# STM32.net
KiCad netlist of a schematic drawn in EasyEDA Pro
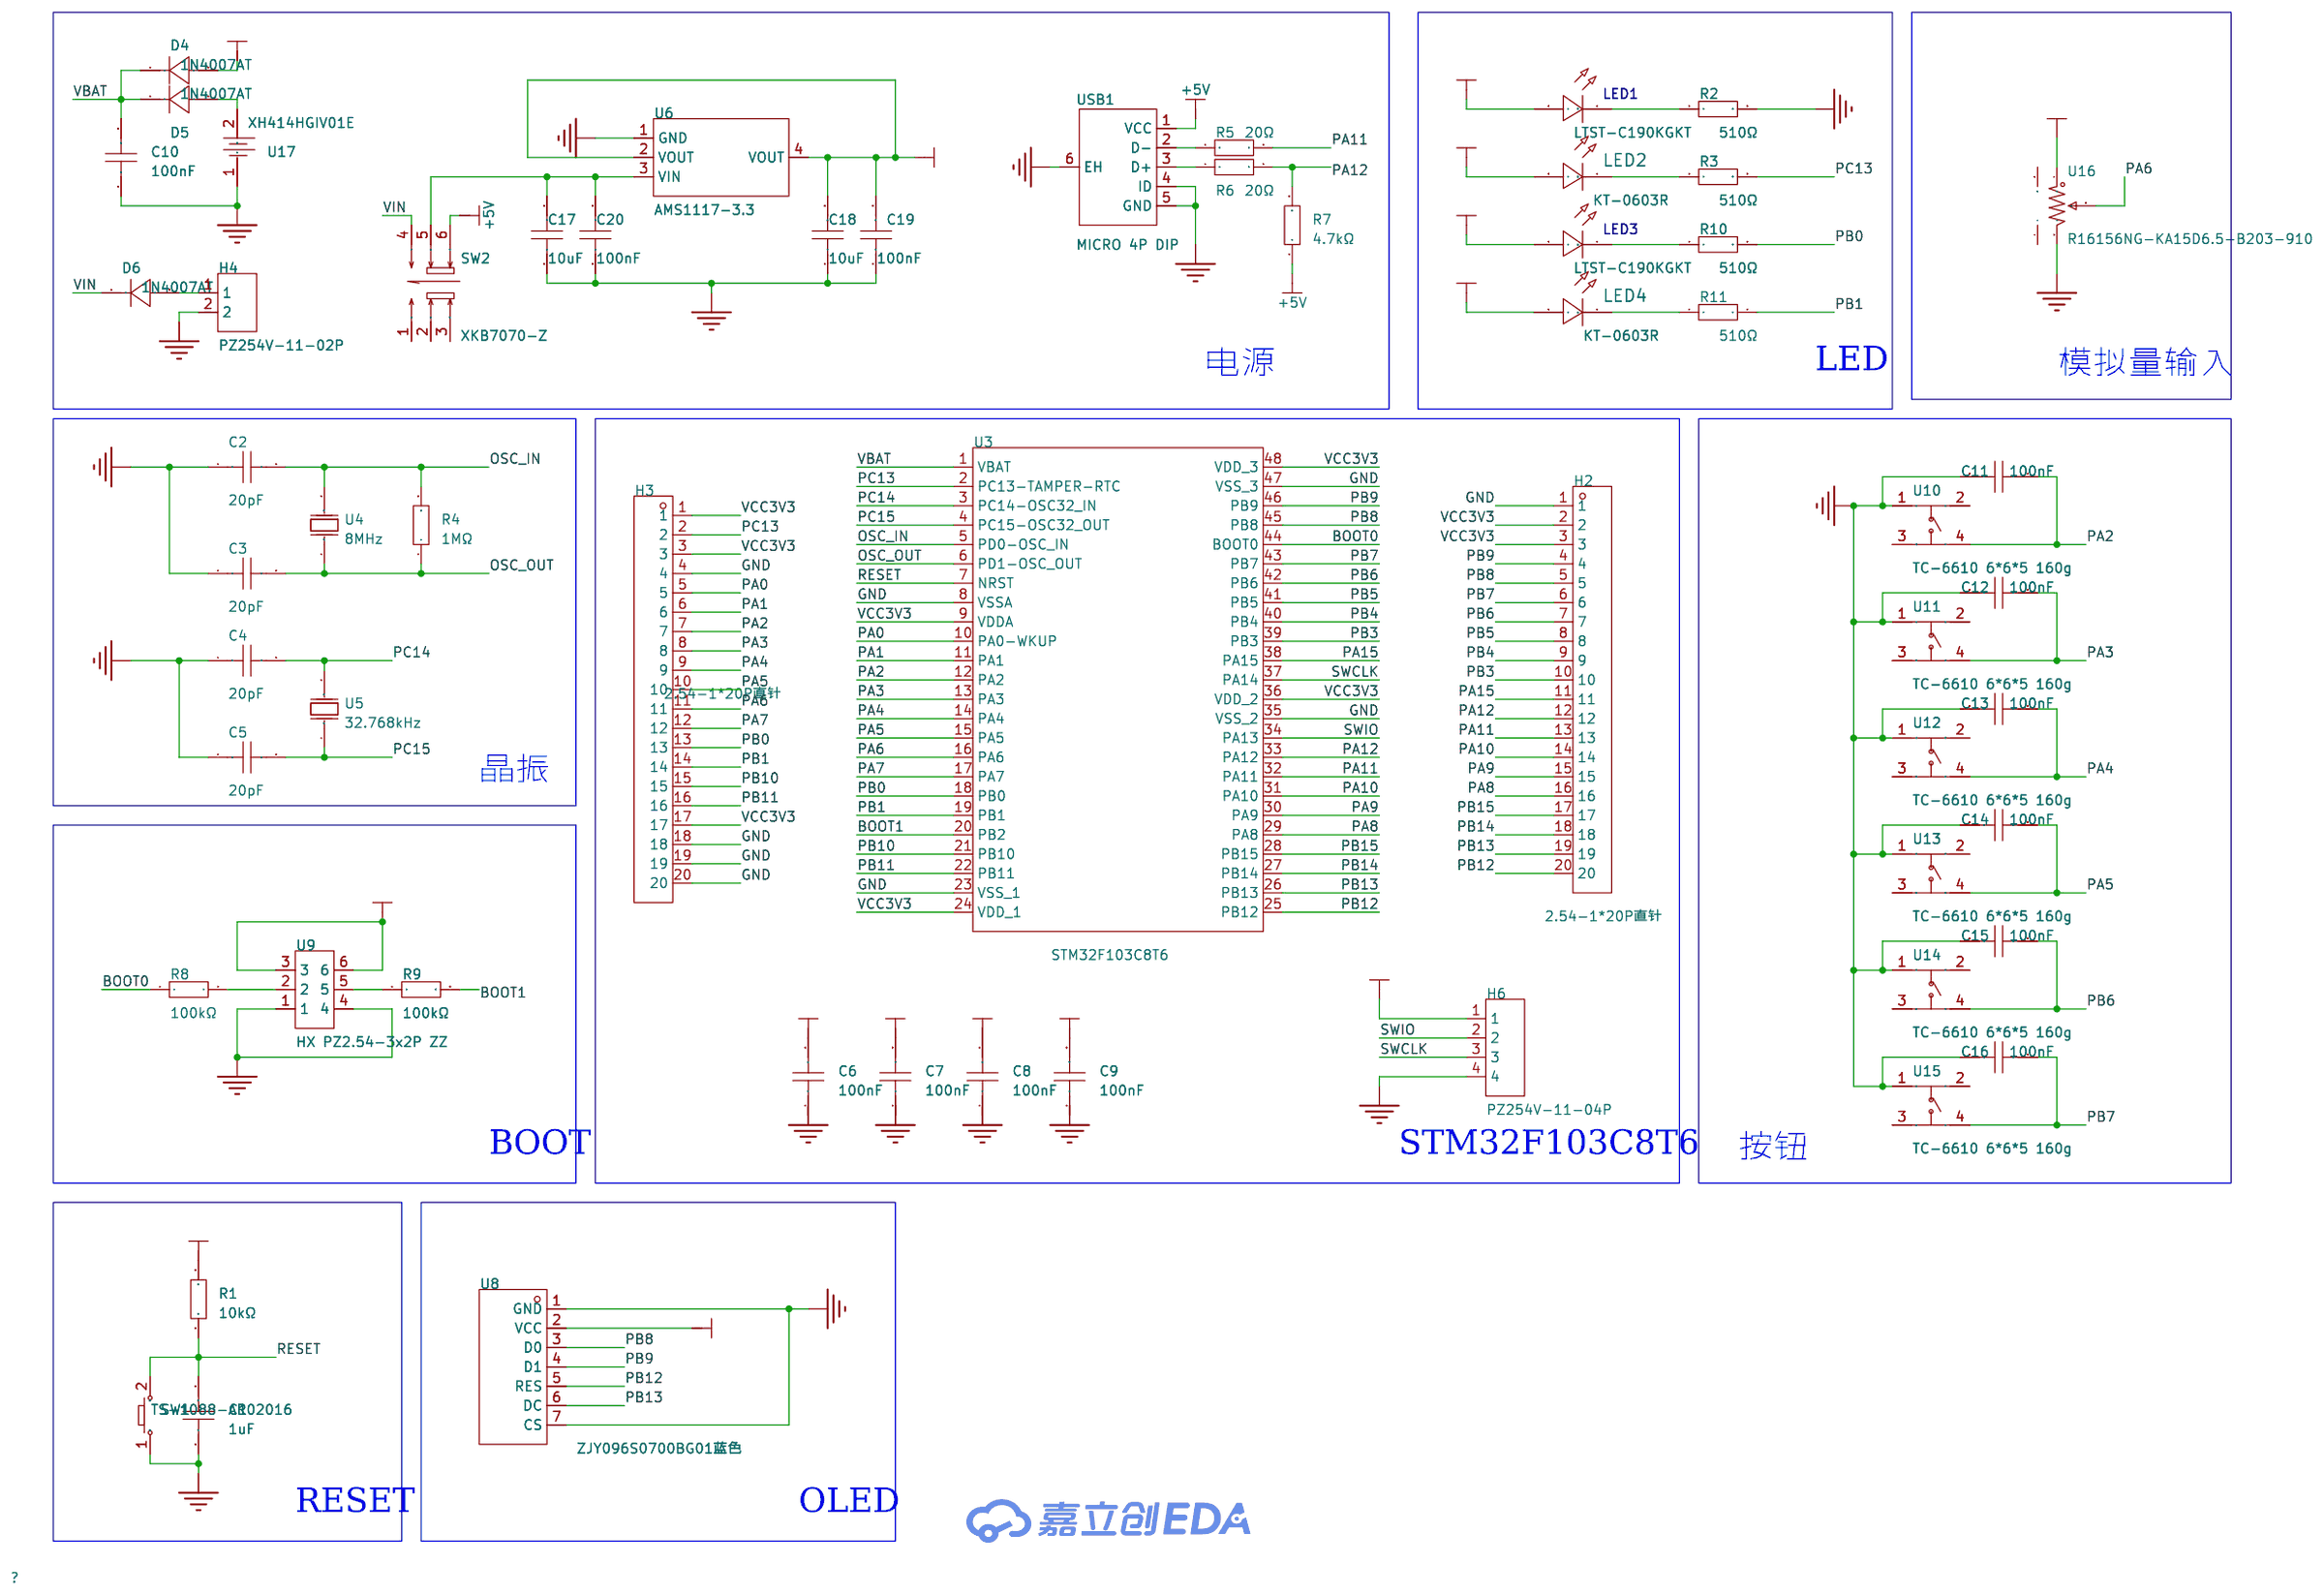
[diagram p0: schematic sheet]

(export (version "E")
  (design (tool "Eeschema 10.0.6"))
  (components
    (comp (ref "C1")
      (value "1uF")
      (footprint "easyedapro:C0603")
      (fields
        (field (name "Manufacturer Part") "CL10A105KO8NNNC")
        (field (name "Manufacturer") "SAMSUNG(三星)")
      )
      (libsource (lib "easyedapro") (part "Capacitance"))
    )
    (comp (ref "C2")
      (value "20pF")
      (footprint "easyedapro:C0603")
      (fields
        (field (name "Manufacturer Part") "CC0603JRNPO9BN200")
        (field (name "Manufacturer") "YAGEO(国巨)")
      )
      (libsource (lib "easyedapro") (part "Capacitance"))
    )
    (comp (ref "C3")
      (value "20pF")
      (footprint "easyedapro:C0603")
      (fields
        (field (name "Manufacturer Part") "CC0603JRNPO9BN200")
        (field (name "Manufacturer") "YAGEO(国巨)")
      )
      (libsource (lib "easyedapro") (part "Capacitance"))
    )
    (comp (ref "C4")
      (value "20pF")
      (footprint "easyedapro:C0603")
      (fields
        (field (name "Manufacturer Part") "CC0603JRNPO9BN200")
        (field (name "Manufacturer") "YAGEO(国巨)")
      )
      (libsource (lib "easyedapro") (part "Capacitance"))
    )
    (comp (ref "C5")
      (value "20pF")
      (footprint "easyedapro:C0603")
      (fields
        (field (name "Manufacturer Part") "CC0603JRNPO9BN200")
        (field (name "Manufacturer") "YAGEO(国巨)")
      )
      (libsource (lib "easyedapro") (part "Capacitance"))
    )
    (comp (ref "C6")
      (value "100nF")
      (footprint "easyedapro:C0603")
      (fields
        (field (name "Manufacturer Part") "CGA0603X7R104K500JT")
        (field (name "Manufacturer") "HRE(芯声)")
      )
      (libsource (lib "easyedapro") (part "Capacitance"))
    )
    (comp (ref "C7")
      (value "100nF")
      (footprint "easyedapro:C0603")
      (fields
        (field (name "Manufacturer Part") "CGA0603X7R104K500JT")
        (field (name "Manufacturer") "HRE(芯声)")
      )
      (libsource (lib "easyedapro") (part "Capacitance"))
    )
    (comp (ref "C8")
      (value "100nF")
      (footprint "easyedapro:C0603")
      (fields
        (field (name "Manufacturer Part") "CGA0603X7R104K500JT")
        (field (name "Manufacturer") "HRE(芯声)")
      )
      (libsource (lib "easyedapro") (part "Capacitance"))
    )
    (comp (ref "C9")
      (value "100nF")
      (footprint "easyedapro:C0603")
      (fields
        (field (name "Manufacturer Part") "CGA0603X7R104K500JT")
        (field (name "Manufacturer") "HRE(芯声)")
      )
      (libsource (lib "easyedapro") (part "Capacitance"))
    )
    (comp (ref "C10")
      (value "100nF")
      (footprint "easyedapro:C0603")
      (fields
        (field (name "Manufacturer Part") "CGA0603X7R104K500JT")
        (field (name "Manufacturer") "HRE(芯声)")
      )
      (libsource (lib "easyedapro") (part "Capacitance"))
    )
    (comp (ref "C11")
      (value "100nF")
      (footprint "easyedapro:C0603")
      (fields
        (field (name "Manufacturer Part") "CL10B104KA8NNNC")
        (field (name "Manufacturer") "SAMSUNG(三星)")
      )
      (libsource (lib "easyedapro") (part "Capacitance"))
    )
    (comp (ref "C12")
      (value "100nF")
      (footprint "easyedapro:C0603")
      (fields
        (field (name "Manufacturer Part") "CL10B104KA8NNNC")
        (field (name "Manufacturer") "SAMSUNG(三星)")
      )
      (libsource (lib "easyedapro") (part "Capacitance"))
    )
    (comp (ref "C13")
      (value "100nF")
      (footprint "easyedapro:C0603")
      (fields
        (field (name "Manufacturer Part") "CL10B104KA8NNNC")
        (field (name "Manufacturer") "SAMSUNG(三星)")
      )
      (libsource (lib "easyedapro") (part "Capacitance"))
    )
    (comp (ref "C14")
      (value "100nF")
      (footprint "easyedapro:C0603")
      (fields
        (field (name "Manufacturer Part") "CL10B104KA8NNNC")
        (field (name "Manufacturer") "SAMSUNG(三星)")
      )
      (libsource (lib "easyedapro") (part "Capacitance"))
    )
    (comp (ref "C15")
      (value "100nF")
      (footprint "easyedapro:C0603")
      (fields
        (field (name "Manufacturer Part") "CL10B104KA8NNNC")
        (field (name "Manufacturer") "SAMSUNG(三星)")
      )
      (libsource (lib "easyedapro") (part "Capacitance"))
    )
    (comp (ref "C16")
      (value "100nF")
      (footprint "easyedapro:C0603")
      (fields
        (field (name "Manufacturer Part") "CL10B104KA8NNNC")
        (field (name "Manufacturer") "SAMSUNG(三星)")
      )
      (libsource (lib "easyedapro") (part "Capacitance"))
    )
    (comp (ref "C17")
      (value "10uF")
      (footprint "easyedapro:C0603")
      (fields
        (field (name "Manufacturer Part") "CL10A106KP8NNNC")
        (field (name "Manufacturer") "SAMSUNG(三星)")
      )
      (libsource (lib "easyedapro") (part "Capacitance"))
    )
    (comp (ref "C18")
      (value "10uF")
      (footprint "easyedapro:C0603")
      (fields
        (field (name "Manufacturer Part") "CL10A106KP8NNNC")
        (field (name "Manufacturer") "SAMSUNG(三星)")
      )
      (libsource (lib "easyedapro") (part "Capacitance"))
    )
    (comp (ref "C19")
      (value "100nF")
      (footprint "easyedapro:C0603")
      (fields
        (field (name "Manufacturer Part") "CL10B104KA8NNNC")
        (field (name "Manufacturer") "SAMSUNG(三星)")
      )
      (libsource (lib "easyedapro") (part "Capacitance"))
    )
    (comp (ref "C20")
      (value "100nF")
      (footprint "easyedapro:C0603")
      (fields
        (field (name "Manufacturer Part") "CL10B104KA8NNNC")
        (field (name "Manufacturer") "SAMSUNG(三星)")
      )
      (libsource (lib "easyedapro") (part "Capacitance"))
    )
    (comp (ref "D4")
      (value "1N4007AT")
      (footprint "easyedapro:DO_1N4007")
      (fields (field (name "Manufacturer") "Agertech(艾吉芯)"))
      (libsource (lib "easyedapro") (part "D_1N4007"))
    )
    (comp (ref "D5")
      (value "1N4007AT")
      (footprint "easyedapro:DO_1N4007")
      (fields (field (name "Manufacturer") "Agertech(艾吉芯)"))
      (libsource (lib "easyedapro") (part "D_1N4007"))
    )
    (comp (ref "D6")
      (value "1N4007AT")
      (footprint "easyedapro:DO_1N4007")
      (fields (field (name "Manufacturer") "Agertech(艾吉芯)"))
      (libsource (lib "easyedapro") (part "D_1N4007"))
    )
    (comp (ref "H2")
      (value "2.54-1*20P直针")
      (footprint "easyedapro:HDR-TH_20P-P2.54-V-M-1")
      (fields (field (name "Manufacturer") "BOOMELE(博穆精密)"))
      (libsource (lib "easyedapro") (part "HDR_2.54-1x20P"))
    )
    (comp (ref "H3")
      (value "2.54-1*20P直针")
      (footprint "easyedapro:HDR-TH_20P-P2.54-V-M-1")
      (fields (field (name "Manufacturer") "BOOMELE(博穆精密)"))
      (libsource (lib "easyedapro") (part "HDR_2.54-1x20P"))
    )
    (comp (ref "H4")
      (value "PZ254V-11-02P")
      (footprint "easyedapro:HDR-TH_2P-P2.54-V-M")
      (fields (field (name "Manufacturer") "XFCN(兴飞)"))
      (libsource (lib "easyedapro") (part "PZ254V-11-02P"))
    )
    (comp (ref "H6")
      (value "PZ254V-11-04P")
      (footprint "easyedapro:HDR-TH_4P-P2.54-V-M")
      (fields (field (name "Manufacturer") "XFCN(兴飞)"))
      (libsource (lib "easyedapro") (part "PZ254V-11-04P"))
    )
    (comp (ref "LED1")
      (value "LTST-C190KGKT")
      (footprint "easyedapro:LED_0603")
      (fields (field (name "Manufacturer") "LITEON(光宝)"))
      (libsource (lib "easyedapro") (part "LED_G"))
    )
    (comp (ref "LED2")
      (value "KT-0603R")
      (footprint "easyedapro:LED_0603")
      (fields (field (name "Manufacturer") "KENTO"))
      (libsource (lib "easyedapro") (part "LED_R"))
    )
    (comp (ref "LED3")
      (value "LTST-C190KGKT")
      (footprint "easyedapro:LED_0603")
      (fields (field (name "Manufacturer") "LITEON(光宝)"))
      (libsource (lib "easyedapro") (part "LED_G"))
    )
    (comp (ref "LED4")
      (value "KT-0603R")
      (footprint "easyedapro:LED_0603")
      (fields (field (name "Manufacturer") "KENTO"))
      (libsource (lib "easyedapro") (part "LED_R"))
    )
    (comp (ref "R1")
      (value "10kΩ")
      (footprint "easyedapro:R0603")
      (fields
        (field (name "Manufacturer Part") "0603WAF1002T5E")
        (field (name "Manufacturer") "UNI-ROYAL(厚声)")
      )
      (libsource (lib "easyedapro") (part "电阻"))
    )
    (comp (ref "R2")
      (value "510Ω")
      (footprint "easyedapro:R0603")
      (fields
        (field (name "Manufacturer Part") "0603WAF5100T5E")
        (field (name "Manufacturer") "UNI-ROYAL(厚声)")
      )
      (libsource (lib "easyedapro") (part "电阻"))
    )
    (comp (ref "R3")
      (value "510Ω")
      (footprint "easyedapro:R0603")
      (fields
        (field (name "Manufacturer Part") "0603WAF5100T5E")
        (field (name "Manufacturer") "UNI-ROYAL(厚声)")
      )
      (libsource (lib "easyedapro") (part "电阻"))
    )
    (comp (ref "R4")
      (value "1MΩ")
      (footprint "easyedapro:R0603")
      (fields
        (field (name "Manufacturer Part") "0603WAF1004T5E")
        (field (name "Manufacturer") "UNI-ROYAL(厚声)")
      )
      (libsource (lib "easyedapro") (part "电阻"))
    )
    (comp (ref "R5")
      (value "20Ω")
      (footprint "easyedapro:R0603")
      (fields
        (field (name "Manufacturer Part") "0603WAF200JT5E")
        (field (name "Manufacturer") "UNI-ROYAL(厚声)")
      )
      (libsource (lib "easyedapro") (part "电阻"))
    )
    (comp (ref "R6")
      (value "20Ω")
      (footprint "easyedapro:R0603")
      (fields
        (field (name "Manufacturer Part") "0603WAF200JT5E")
        (field (name "Manufacturer") "UNI-ROYAL(厚声)")
      )
      (libsource (lib "easyedapro") (part "电阻"))
    )
    (comp (ref "R7")
      (value "4.7kΩ")
      (footprint "easyedapro:R0603")
      (fields
        (field (name "Manufacturer Part") "0603WAF4701T5E")
        (field (name "Manufacturer") "UNI-ROYAL(厚声)")
      )
      (libsource (lib "easyedapro") (part "电阻"))
    )
    (comp (ref "R8")
      (value "100kΩ")
      (footprint "easyedapro:R0603")
      (fields
        (field (name "Manufacturer Part") "0603WAF1003T5E")
        (field (name "Manufacturer") "UNI-ROYAL(厚声)")
      )
      (libsource (lib "easyedapro") (part "电阻"))
    )
    (comp (ref "R9")
      (value "100kΩ")
      (footprint "easyedapro:R0603")
      (fields
        (field (name "Manufacturer Part") "0603WAF1003T5E")
        (field (name "Manufacturer") "UNI-ROYAL(厚声)")
      )
      (libsource (lib "easyedapro") (part "电阻"))
    )
    (comp (ref "R10")
      (value "510Ω")
      (footprint "easyedapro:R0603")
      (fields
        (field (name "Manufacturer Part") "0603WAF5100T5E")
        (field (name "Manufacturer") "UNI-ROYAL(厚声)")
      )
      (libsource (lib "easyedapro") (part "电阻"))
    )
    (comp (ref "R11")
      (value "510Ω")
      (footprint "easyedapro:R0603")
      (fields
        (field (name "Manufacturer Part") "0603WAF5100T5E")
        (field (name "Manufacturer") "UNI-ROYAL(厚声)")
      )
      (libsource (lib "easyedapro") (part "电阻"))
    )
    (comp (ref "SW1")
      (value "TS-1088-AR02016")
      (footprint "easyedapro:Key_SMD_3x4x2")
      (fields (field (name "Manufacturer") "XUNPU(讯普)"))
      (libsource (lib "easyedapro") (part "轻触按键x2"))
    )
    (comp (ref "SW2")
      (value "XKB7070-Z")
      (footprint "easyedapro:SW-TH_6P-L7.0-W7.0-P2.00")
      (description "自锁/无锁:自锁;安装方式:直插;触点电流:100mA;额定电压 (AC):250V;额定电压 (DC):30V;带灯:不带;作用力:160gf;机械寿命:10万次;")
      (fields (field (name "Manufacturer") "XKB Connectivity(中国星坤)"))
      (libsource (lib "easyedapro") (part "XKB7070-Z"))
    )
    (comp (ref "U3")
      (value "STM32F103C8T6")
      (footprint "easyedapro:LQFP-48_L7.0-W7.0-P0.50-LS9.0-BL")
      (description "CPU内核:ARM-M3;CPU最大主频:72MHz;应用领域:-;")
      (fields (field (name "Manufacturer") "ST(意法半导体)"))
      (libsource (lib "easyedapro") (part "STM32F103C8T6"))
    )
    (comp (ref "U4")
      (value "8MHz")
      (footprint "easyedapro:HC-49S_L11.5-W5.0-P4.88")
      (description "频率:8MHz;常温频差:±20ppm;外接负载电容:20pF;频率稳定度(全温):±30ppm;")
      (fields (field (name "Manufacturer Part") "RB080001184") (field (name "Manufacturer") "TROQ(创捷)"))
      (libsource (lib "easyedapro") (part "RB080001184"))
    )
    (comp (ref "U5")
      (value "32.768kHz")
      (footprint "easyedapro:CRYSTAL-SMD_L3.2-W1.5")
      (description "晶振类型:贴片晶振;频率:32.768kHz;常温频差:±10ppm;外接负载电容:12.5pF;")
      (fields (field (name "Manufacturer Part") "RNE32768082") (field (name "Manufacturer") "TROQ(创捷)"))
      (libsource (lib "easyedapro") (part "RNE32768082"))
    )
    (comp (ref "U6")
      (value "AMS1117-3.3")
      (footprint "easyedapro:SOT-223-3_L6.5-W3.4-P2.30-LS7.0-BR")
      (description "输出类型:固定;工作电压:16V;输出电压:3.3V;输出电流:1A;电源纹波抑制比(PSRR):72dB@(120Hz);输出极性:正极;")
      (fields (field (name "Manufacturer") "AMS"))
      (libsource (lib "easyedapro") (part "AMS1117-3.3"))
    )
    (comp (ref "U8")
      (value "ZJY096S0700BG01蓝色")
      (footprint "easyedapro:OLED-TH_OLED0.96-SPI")
      (libsource (lib "easyedapro") (part "ZJY096S0700BG01蓝色"))
    )
    (comp (ref "U9")
      (value "HX PZ2.54-3x2P ZZ")
      (footprint "easyedapro:HDR-TH_6P-P2.54-V-M-R3-C2-S2.54_2")
      (fields (field (name "Manufacturer") "hanxia(韩下)"))
      (libsource (lib "easyedapro") (part "HX PZ2.54-3X2P ZZ"))
    )
    (comp (ref "U10")
      (value "TC-6610 6*6*5 160g")
      (footprint "easyedapro:SW-TH_4P-L6.0-W6.0-P4.50-LS6.5")
      (description "轻触开关  6*6*5 160g力 4.3基座 复银 耐温 ROHS")
      (fields (field (name "Manufacturer") "FG(富港)"))
      (libsource (lib "easyedapro") (part "TC-6610 6*6*5 160G"))
    )
    (comp (ref "U11")
      (value "TC-6610 6*6*5 160g")
      (footprint "easyedapro:SW-TH_4P-L6.0-W6.0-P4.50-LS6.5")
      (description "轻触开关  6*6*5 160g力 4.3基座 复银 耐温 ROHS")
      (fields (field (name "Manufacturer") "FG(富港)"))
      (libsource (lib "easyedapro") (part "TC-6610 6*6*5 160G"))
    )
    (comp (ref "U12")
      (value "TC-6610 6*6*5 160g")
      (footprint "easyedapro:SW-TH_4P-L6.0-W6.0-P4.50-LS6.5")
      (description "轻触开关  6*6*5 160g力 4.3基座 复银 耐温 ROHS")
      (fields (field (name "Manufacturer") "FG(富港)"))
      (libsource (lib "easyedapro") (part "TC-6610 6*6*5 160G"))
    )
    (comp (ref "U13")
      (value "TC-6610 6*6*5 160g")
      (footprint "easyedapro:SW-TH_4P-L6.0-W6.0-P4.50-LS6.5")
      (description "轻触开关  6*6*5 160g力 4.3基座 复银 耐温 ROHS")
      (fields (field (name "Manufacturer") "FG(富港)"))
      (libsource (lib "easyedapro") (part "TC-6610 6*6*5 160G"))
    )
    (comp (ref "U14")
      (value "TC-6610 6*6*5 160g")
      (footprint "easyedapro:SW-TH_4P-L6.0-W6.0-P4.50-LS6.5")
      (description "轻触开关  6*6*5 160g力 4.3基座 复银 耐温 ROHS")
      (fields (field (name "Manufacturer") "FG(富港)"))
      (libsource (lib "easyedapro") (part "TC-6610 6*6*5 160G"))
    )
    (comp (ref "U15")
      (value "TC-6610 6*6*5 160g")
      (footprint "easyedapro:SW-TH_4P-L6.0-W6.0-P4.50-LS6.5")
      (description "轻触开关  6*6*5 160g力 4.3基座 复银 耐温 ROHS")
      (fields (field (name "Manufacturer") "FG(富港)"))
      (libsource (lib "easyedapro") (part "TC-6610 6*6*5 160G"))
    )
    (comp (ref "U16")
      (value "R16156NG-KA15D6.5-B203-910")
      (footprint "easyedapro:RES-ADJ-TH_R16156NG-KA15D6.5-B203-910")
      (description "可调电阻旋转电位器单联，旋转角度：300+/-5°，旋转寿命：10000次，使用温度：-10°~+70°")
      (fields (field (name "Manufacturer") "CTR(长泰尔电子)"))
      (libsource (lib "easyedapro") (part "R16156NG-KA15D6.5-B203-910"))
    )
    (comp (ref "U17")
      (value "XH414HGIV01E")
      (footprint "easyedapro:CAP-SMD_2P-L4.8-W4.8-TR")
      (fields (field (name "Manufacturer") "Seiko(精工)"))
      (libsource (lib "easyedapro") (part "XH414HGIV01E"))
    )
    (comp (ref "USB1")
      (value "MICRO 4P DIP")
      (footprint "easyedapro:USB_Micro")
      (fields (field (name "Manufacturer") "SHOU HAN(首韩)"))
      (libsource (lib "easyedapro") (part "USB_Micro"))
    )
  )
  (nets
    (net (code "1") (name "+5V") (class "Default")
      (node (ref "R7") (pin "1") (pinfunction "1_1") (pintype "input"))
      (node (ref "SW2") (pin "6") (pinfunction "6_6") (pintype "unspecified"))
      (node (ref "USB1") (pin "1") (pinfunction "VCC_1") (pintype "input"))
    )
    (net (code "2") (name "/BOOT0") (class "Default")
      (node (ref "R8") (pin "1") (pinfunction "1_1") (pintype "input"))
      (node (ref "U3") (pin "44") (pinfunction "BOOT0_44") (pintype "unspecified"))
    )
    (net (code "3") (name "/BOOT1") (class "Default")
      (node (ref "R9") (pin "2") (pinfunction "2_2") (pintype "input"))
      (node (ref "U3") (pin "20") (pinfunction "PB2_20") (pintype "unspecified"))
    )
    (net (code "4") (name "/OSC_IN") (class "Default")
      (node (ref "C2") (pin "2") (pinfunction "2_2") (pintype "input"))
      (node (ref "R4") (pin "2") (pinfunction "2_2") (pintype "input"))
      (node (ref "U3") (pin "5") (pinfunction "PD0-OSC_IN_5") (pintype "unspecified"))
      (node (ref "U4") (pin "2") (pinfunction "OSC2_2") (pintype "input"))
    )
    (net (code "5") (name "/OSC_OUT") (class "Default")
      (node (ref "C3") (pin "2") (pinfunction "2_2") (pintype "input"))
      (node (ref "R4") (pin "1") (pinfunction "1_1") (pintype "input"))
      (node (ref "U3") (pin "6") (pinfunction "PD1-OSC_OUT_6") (pintype "unspecified"))
      (node (ref "U4") (pin "1") (pinfunction "OSC1_1") (pintype "input"))
    )
    (net (code "6") (name "/PA0") (class "Default")
      (node (ref "H3") (pin "5") (pinfunction "5_5") (pintype "input"))
      (node (ref "U3") (pin "10") (pinfunction "PA0-WKUP_10") (pintype "unspecified"))
    )
    (net (code "7") (name "/PA1") (class "Default")
      (node (ref "H3") (pin "6") (pinfunction "6_6") (pintype "input"))
      (node (ref "U3") (pin "11") (pinfunction "PA1_11") (pintype "unspecified"))
    )
    (net (code "8") (name "/PA2") (class "Default")
      (node (ref "C11") (pin "1") (pinfunction "1_1") (pintype "input"))
      (node (ref "H3") (pin "7") (pinfunction "7_7") (pintype "input"))
      (node (ref "U10") (pin "4") (pinfunction "4_4") (pintype "unspecified"))
      (node (ref "U3") (pin "12") (pinfunction "PA2_12") (pintype "unspecified"))
    )
    (net (code "9") (name "/PA3") (class "Default")
      (node (ref "C12") (pin "1") (pinfunction "1_1") (pintype "input"))
      (node (ref "H3") (pin "8") (pinfunction "8_8") (pintype "input"))
      (node (ref "U11") (pin "4") (pinfunction "4_4") (pintype "unspecified"))
      (node (ref "U3") (pin "13") (pinfunction "PA3_13") (pintype "unspecified"))
    )
    (net (code "10") (name "/PA4") (class "Default")
      (node (ref "C13") (pin "1") (pinfunction "1_1") (pintype "input"))
      (node (ref "H3") (pin "9") (pinfunction "9_9") (pintype "input"))
      (node (ref "U12") (pin "4") (pinfunction "4_4") (pintype "unspecified"))
      (node (ref "U3") (pin "14") (pinfunction "PA4_14") (pintype "unspecified"))
    )
    (net (code "11") (name "/PA5") (class "Default")
      (node (ref "C14") (pin "1") (pinfunction "1_1") (pintype "input"))
      (node (ref "H3") (pin "10") (pinfunction "10_10") (pintype "input"))
      (node (ref "U13") (pin "4") (pinfunction "4_4") (pintype "unspecified"))
      (node (ref "U3") (pin "15") (pinfunction "PA5_15") (pintype "unspecified"))
    )
    (net (code "12") (name "/PA6") (class "Default")
      (node (ref "H3") (pin "11") (pinfunction "11_11") (pintype "input"))
      (node (ref "U16") (pin "2") (pinfunction "2_2") (pintype "unspecified"))
      (node (ref "U3") (pin "16") (pinfunction "PA6_16") (pintype "unspecified"))
    )
    (net (code "13") (name "/PA7") (class "Default")
      (node (ref "H3") (pin "12") (pinfunction "12_12") (pintype "input"))
      (node (ref "U3") (pin "17") (pinfunction "PA7_17") (pintype "unspecified"))
    )
    (net (code "14") (name "/PA8") (class "Default")
      (node (ref "H2") (pin "16") (pinfunction "16_16") (pintype "input"))
      (node (ref "U3") (pin "29") (pinfunction "PA8_29") (pintype "unspecified"))
    )
    (net (code "15") (name "/PA9") (class "Default")
      (node (ref "H2") (pin "15") (pinfunction "15_15") (pintype "input"))
      (node (ref "U3") (pin "30") (pinfunction "PA9_30") (pintype "unspecified"))
    )
    (net (code "16") (name "/PA10") (class "Default")
      (node (ref "H2") (pin "14") (pinfunction "14_14") (pintype "input"))
      (node (ref "U3") (pin "31") (pinfunction "PA10_31") (pintype "unspecified"))
    )
    (net (code "17") (name "/PA11") (class "Default")
      (node (ref "H2") (pin "13") (pinfunction "13_13") (pintype "input"))
      (node (ref "R5") (pin "2") (pinfunction "2_2") (pintype "input"))
      (node (ref "U3") (pin "32") (pinfunction "PA11_32") (pintype "unspecified"))
    )
    (net (code "18") (name "/PA12") (class "Default")
      (node (ref "H2") (pin "12") (pinfunction "12_12") (pintype "input"))
      (node (ref "R6") (pin "2") (pinfunction "2_2") (pintype "input"))
      (node (ref "R7") (pin "2") (pinfunction "2_2") (pintype "input"))
      (node (ref "U3") (pin "33") (pinfunction "PA12_33") (pintype "unspecified"))
    )
    (net (code "19") (name "/PA15") (class "Default")
      (node (ref "H2") (pin "11") (pinfunction "11_11") (pintype "input"))
      (node (ref "U3") (pin "38") (pinfunction "PA15_38") (pintype "unspecified"))
    )
    (net (code "20") (name "/PB0") (class "Default")
      (node (ref "H3") (pin "13") (pinfunction "13_13") (pintype "input"))
      (node (ref "R10") (pin "2") (pinfunction "2_2") (pintype "input"))
      (node (ref "U3") (pin "18") (pinfunction "PB0_18") (pintype "unspecified"))
    )
    (net (code "21") (name "/PB1") (class "Default")
      (node (ref "H3") (pin "14") (pinfunction "14_14") (pintype "input"))
      (node (ref "R11") (pin "2") (pinfunction "2_2") (pintype "input"))
      (node (ref "U3") (pin "19") (pinfunction "PB1_19") (pintype "unspecified"))
    )
    (net (code "22") (name "/PB3") (class "Default")
      (node (ref "H2") (pin "10") (pinfunction "10_10") (pintype "input"))
      (node (ref "U3") (pin "39") (pinfunction "PB3_39") (pintype "unspecified"))
    )
    (net (code "23") (name "/PB4") (class "Default")
      (node (ref "H2") (pin "9") (pinfunction "9_9") (pintype "input"))
      (node (ref "U3") (pin "40") (pinfunction "PB4_40") (pintype "unspecified"))
    )
    (net (code "24") (name "/PB5") (class "Default")
      (node (ref "H2") (pin "8") (pinfunction "8_8") (pintype "input"))
      (node (ref "U3") (pin "41") (pinfunction "PB5_41") (pintype "unspecified"))
    )
    (net (code "25") (name "/PB6") (class "Default")
      (node (ref "C15") (pin "1") (pinfunction "1_1") (pintype "input"))
      (node (ref "H2") (pin "7") (pinfunction "7_7") (pintype "input"))
      (node (ref "U14") (pin "4") (pinfunction "4_4") (pintype "unspecified"))
      (node (ref "U3") (pin "42") (pinfunction "PB6_42") (pintype "unspecified"))
    )
    (net (code "26") (name "/PB7") (class "Default")
      (node (ref "C16") (pin "1") (pinfunction "1_1") (pintype "input"))
      (node (ref "H2") (pin "6") (pinfunction "6_6") (pintype "input"))
      (node (ref "U15") (pin "4") (pinfunction "4_4") (pintype "unspecified"))
      (node (ref "U3") (pin "43") (pinfunction "PB7_43") (pintype "unspecified"))
    )
    (net (code "27") (name "/PB8") (class "Default")
      (node (ref "H2") (pin "5") (pinfunction "5_5") (pintype "input"))
      (node (ref "U3") (pin "45") (pinfunction "PB8_45") (pintype "unspecified"))
      (node (ref "U8") (pin "3") (pinfunction "D0_3") (pintype "unspecified"))
    )
    (net (code "28") (name "/PB9") (class "Default")
      (node (ref "H2") (pin "4") (pinfunction "4_4") (pintype "input"))
      (node (ref "U3") (pin "46") (pinfunction "PB9_46") (pintype "unspecified"))
      (node (ref "U8") (pin "4") (pinfunction "D1_4") (pintype "unspecified"))
    )
    (net (code "29") (name "/PB10") (class "Default")
      (node (ref "H3") (pin "15") (pinfunction "15_15") (pintype "input"))
      (node (ref "U3") (pin "21") (pinfunction "PB10_21") (pintype "unspecified"))
    )
    (net (code "30") (name "/PB11") (class "Default")
      (node (ref "H3") (pin "16") (pinfunction "16_16") (pintype "input"))
      (node (ref "U3") (pin "22") (pinfunction "PB11_22") (pintype "unspecified"))
    )
    (net (code "31") (name "/PB12") (class "Default")
      (node (ref "H2") (pin "20") (pinfunction "20_20") (pintype "input"))
      (node (ref "U3") (pin "25") (pinfunction "PB12_25") (pintype "unspecified"))
      (node (ref "U8") (pin "5") (pinfunction "RES_5") (pintype "unspecified"))
    )
    (net (code "32") (name "/PB13") (class "Default")
      (node (ref "H2") (pin "19") (pinfunction "19_19") (pintype "input"))
      (node (ref "U3") (pin "26") (pinfunction "PB13_26") (pintype "unspecified"))
      (node (ref "U8") (pin "6") (pinfunction "DC_6") (pintype "unspecified"))
    )
    (net (code "33") (name "/PB14") (class "Default")
      (node (ref "H2") (pin "18") (pinfunction "18_18") (pintype "input"))
      (node (ref "U3") (pin "27") (pinfunction "PB14_27") (pintype "unspecified"))
    )
    (net (code "34") (name "/PB15") (class "Default")
      (node (ref "H2") (pin "17") (pinfunction "17_17") (pintype "input"))
      (node (ref "U3") (pin "28") (pinfunction "PB15_28") (pintype "unspecified"))
    )
    (net (code "35") (name "/PC13") (class "Default")
      (node (ref "H3") (pin "2") (pinfunction "2_2") (pintype "input"))
      (node (ref "R3") (pin "2") (pinfunction "2_2") (pintype "input"))
      (node (ref "U3") (pin "2") (pinfunction "PC13-TAMPER-RTC_2") (pintype "unspecified"))
    )
    (net (code "36") (name "/PC14") (class "Default")
      (node (ref "C4") (pin "2") (pinfunction "2_2") (pintype "input"))
      (node (ref "U3") (pin "3") (pinfunction "PC14-OSC32_IN_3") (pintype "unspecified"))
      (node (ref "U5") (pin "2") (pinfunction "OSC2_2") (pintype "input"))
    )
    (net (code "37") (name "/PC15") (class "Default")
      (node (ref "C5") (pin "2") (pinfunction "2_2") (pintype "input"))
      (node (ref "U3") (pin "4") (pinfunction "PC15-OSC32_OUT_4") (pintype "unspecified"))
      (node (ref "U5") (pin "1") (pinfunction "OSC1_1") (pintype "input"))
    )
    (net (code "38") (name "/RESET") (class "Default")
      (node (ref "C1") (pin "2") (pinfunction "2_2") (pintype "input"))
      (node (ref "R1") (pin "1") (pinfunction "1_1") (pintype "input"))
      (node (ref "SW1") (pin "2") (pinfunction "2_2") (pintype "input"))
      (node (ref "U3") (pin "7") (pinfunction "NRST_7") (pintype "unspecified"))
    )
    (net (code "39") (name "/SWCLK") (class "Default")
      (node (ref "H6") (pin "3") (pinfunction "3_3") (pintype "unspecified"))
      (node (ref "U3") (pin "37") (pinfunction "PA14_37") (pintype "unspecified"))
    )
    (net (code "40") (name "/SWIO") (class "Default")
      (node (ref "H6") (pin "2") (pinfunction "2_2") (pintype "unspecified"))
      (node (ref "U3") (pin "34") (pinfunction "PA13_34") (pintype "unspecified"))
    )
    (net (code "41") (name "/VBAT") (class "Default")
      (node (ref "C10") (pin "2") (pinfunction "2_2") (pintype "input"))
      (node (ref "D4") (pin "1") (pinfunction "K_1") (pintype "input"))
      (node (ref "D5") (pin "1") (pinfunction "K_1") (pintype "input"))
      (node (ref "U3") (pin "1") (pinfunction "VBAT_1") (pintype "unspecified"))
    )
    (net (code "42") (name "/VIN") (class "Default")
      (node (ref "D6") (pin "1") (pinfunction "K_1") (pintype "input"))
      (node (ref "SW2") (pin "4") (pinfunction "4_4") (pintype "unspecified"))
    )
    (net (code "43") (name "GND") (class "Default")
      (node (ref "C1") (pin "1") (pinfunction "1_1") (pintype "input"))
      (node (ref "C10") (pin "1") (pinfunction "1_1") (pintype "input"))
      (node (ref "C11") (pin "2") (pinfunction "2_2") (pintype "input"))
      (node (ref "C12") (pin "2") (pinfunction "2_2") (pintype "input"))
      (node (ref "C13") (pin "2") (pinfunction "2_2") (pintype "input"))
      (node (ref "C14") (pin "2") (pinfunction "2_2") (pintype "input"))
      (node (ref "C15") (pin "2") (pinfunction "2_2") (pintype "input"))
      (node (ref "C16") (pin "2") (pinfunction "2_2") (pintype "input"))
      (node (ref "C17") (pin "1") (pinfunction "1_1") (pintype "input"))
      (node (ref "C18") (pin "1") (pinfunction "1_1") (pintype "input"))
      (node (ref "C19") (pin "1") (pinfunction "1_1") (pintype "input"))
      (node (ref "C2") (pin "1") (pinfunction "1_1") (pintype "input"))
      (node (ref "C20") (pin "1") (pinfunction "1_1") (pintype "input"))
      (node (ref "C3") (pin "1") (pinfunction "1_1") (pintype "input"))
      (node (ref "C4") (pin "1") (pinfunction "1_1") (pintype "input"))
      (node (ref "C5") (pin "1") (pinfunction "1_1") (pintype "input"))
      (node (ref "C6") (pin "1") (pinfunction "1_1") (pintype "input"))
      (node (ref "C7") (pin "1") (pinfunction "1_1") (pintype "input"))
      (node (ref "C8") (pin "1") (pinfunction "1_1") (pintype "input"))
      (node (ref "C9") (pin "1") (pinfunction "1_1") (pintype "input"))
      (node (ref "H2") (pin "1") (pinfunction "1_1") (pintype "input"))
      (node (ref "H3") (pin "18") (pinfunction "18_18") (pintype "input"))
      (node (ref "H3") (pin "19") (pinfunction "19_19") (pintype "input"))
      (node (ref "H3") (pin "20") (pinfunction "20_20") (pintype "input"))
      (node (ref "H3") (pin "4") (pinfunction "4_4") (pintype "input"))
      (node (ref "H4") (pin "2") (pinfunction "2_2") (pintype "unspecified"))
      (node (ref "H6") (pin "4") (pinfunction "4_4") (pintype "unspecified"))
      (node (ref "R2") (pin "2") (pinfunction "2_2") (pintype "input"))
      (node (ref "SW1") (pin "1") (pinfunction "1_1") (pintype "input"))
      (node (ref "U10") (pin "1") (pinfunction "1_1") (pintype "unspecified"))
      (node (ref "U11") (pin "1") (pinfunction "1_1") (pintype "unspecified"))
      (node (ref "U12") (pin "1") (pinfunction "1_1") (pintype "unspecified"))
      (node (ref "U13") (pin "1") (pinfunction "1_1") (pintype "unspecified"))
      (node (ref "U14") (pin "1") (pinfunction "1_1") (pintype "unspecified"))
      (node (ref "U15") (pin "1") (pinfunction "1_1") (pintype "unspecified"))
      (node (ref "U16") (pin "3") (pinfunction "3_3") (pintype "unspecified"))
      (node (ref "U17") (pin "1") (pinfunction "1_1") (pintype "input"))
      (node (ref "U3") (pin "23") (pinfunction "VSS_1_23") (pintype "unspecified"))
      (node (ref "U3") (pin "35") (pinfunction "VSS_2_35") (pintype "unspecified"))
      (node (ref "U3") (pin "47") (pinfunction "VSS_3_47") (pintype "unspecified"))
      (node (ref "U3") (pin "8") (pinfunction "VSSA_8") (pintype "unspecified"))
      (node (ref "U6") (pin "1") (pinfunction "GND_1") (pintype "unspecified"))
      (node (ref "U8") (pin "1") (pinfunction "GND_1") (pintype "unspecified"))
      (node (ref "U8") (pin "7") (pinfunction "CS_7") (pintype "unspecified"))
      (node (ref "U9") (pin "1") (pinfunction "1_1") (pintype "unspecified"))
      (node (ref "U9") (pin "4") (pinfunction "4_4") (pintype "unspecified"))
      (node (ref "USB1") (pin "4") (pinfunction "ID_4") (pintype "input"))
      (node (ref "USB1") (pin "5") (pinfunction "GND_5") (pintype "input"))
      (node (ref "USB1") (pin "6") (pinfunction "EH_6") (pintype "input"))
    )
    (net (code "44") (name "Net-(D5-A)") (class "Default")
      (node (ref "D5") (pin "2") (pinfunction "A_2") (pintype "input"))
      (node (ref "U17") (pin "2") (pinfunction "2_2") (pintype "input"))
    )
    (net (code "45") (name "Net-(D6-A)") (class "Default")
      (node (ref "D6") (pin "2") (pinfunction "A_2") (pintype "input"))
      (node (ref "H4") (pin "1") (pinfunction "1_1") (pintype "unspecified"))
    )
    (net (code "46") (name "Net-(LED1-C)") (class "Default")
      (node (ref "LED1") (pin "1") (pinfunction "C_1") (pintype "input"))
      (node (ref "R2") (pin "1") (pinfunction "1_1") (pintype "input"))
    )
    (net (code "47") (name "Net-(LED2-C)") (class "Default")
      (node (ref "LED2") (pin "1") (pinfunction "C_1") (pintype "input"))
      (node (ref "R3") (pin "1") (pinfunction "1_1") (pintype "input"))
    )
    (net (code "48") (name "Net-(LED3-C)") (class "Default")
      (node (ref "LED3") (pin "1") (pinfunction "C_1") (pintype "input"))
      (node (ref "R10") (pin "1") (pinfunction "1_1") (pintype "input"))
    )
    (net (code "49") (name "Net-(LED4-C)") (class "Default")
      (node (ref "LED4") (pin "1") (pinfunction "C_1") (pintype "input"))
      (node (ref "R11") (pin "1") (pinfunction "1_1") (pintype "input"))
    )
    (net (code "50") (name "Net-(R8-Pad2)") (class "Default")
      (node (ref "R8") (pin "2") (pinfunction "2_2") (pintype "input"))
      (node (ref "U9") (pin "2") (pinfunction "2_2") (pintype "unspecified"))
    )
    (net (code "51") (name "Net-(R9-Pad1)") (class "Default")
      (node (ref "R9") (pin "1") (pinfunction "1_1") (pintype "input"))
      (node (ref "U9") (pin "5") (pinfunction "5_5") (pintype "unspecified"))
    )
    (net (code "52") (name "Net-(U6-VIN)") (class "Default")
      (node (ref "C17") (pin "2") (pinfunction "2_2") (pintype "input"))
      (node (ref "C20") (pin "2") (pinfunction "2_2") (pintype "input"))
      (node (ref "SW2") (pin "5") (pinfunction "5_5") (pintype "unspecified"))
      (node (ref "U6") (pin "3") (pinfunction "VIN_3") (pintype "unspecified"))
    )
    (net (code "53") (name "Net-(USB1-D+)") (class "Default")
      (node (ref "R6") (pin "1") (pinfunction "1_1") (pintype "input"))
      (node (ref "USB1") (pin "3") (pinfunction "D+_3") (pintype "input"))
    )
    (net (code "54") (name "Net-(USB1-D-)") (class "Default")
      (node (ref "R5") (pin "1") (pinfunction "1_1") (pintype "input"))
      (node (ref "USB1") (pin "2") (pinfunction "D-_2") (pintype "input"))
    )
    (net (code "55") (name "VCC3V3") (class "Default")
      (node (ref "C18") (pin "2") (pinfunction "2_2") (pintype "input"))
      (node (ref "C19") (pin "2") (pinfunction "2_2") (pintype "input"))
      (node (ref "C6") (pin "2") (pinfunction "2_2") (pintype "input"))
      (node (ref "C7") (pin "2") (pinfunction "2_2") (pintype "input"))
      (node (ref "C8") (pin "2") (pinfunction "2_2") (pintype "input"))
      (node (ref "C9") (pin "2") (pinfunction "2_2") (pintype "input"))
      (node (ref "D4") (pin "2") (pinfunction "A_2") (pintype "input"))
      (node (ref "H2") (pin "2") (pinfunction "2_2") (pintype "input"))
      (node (ref "H2") (pin "3") (pinfunction "3_3") (pintype "input"))
      (node (ref "H3") (pin "1") (pinfunction "1_1") (pintype "input"))
      (node (ref "H3") (pin "17") (pinfunction "17_17") (pintype "input"))
      (node (ref "H3") (pin "3") (pinfunction "3_3") (pintype "input"))
      (node (ref "H6") (pin "1") (pinfunction "1_1") (pintype "unspecified"))
      (node (ref "LED1") (pin "2") (pinfunction "A_2") (pintype "input"))
      (node (ref "LED2") (pin "2") (pinfunction "A_2") (pintype "input"))
      (node (ref "LED3") (pin "2") (pinfunction "A_2") (pintype "input"))
      (node (ref "LED4") (pin "2") (pinfunction "A_2") (pintype "input"))
      (node (ref "R1") (pin "2") (pinfunction "2_2") (pintype "input"))
      (node (ref "U16") (pin "1") (pinfunction "1_1") (pintype "unspecified"))
      (node (ref "U3") (pin "24") (pinfunction "VDD_1_24") (pintype "unspecified"))
      (node (ref "U3") (pin "36") (pinfunction "VDD_2_36") (pintype "unspecified"))
      (node (ref "U3") (pin "48") (pinfunction "VDD_3_48") (pintype "unspecified"))
      (node (ref "U3") (pin "9") (pinfunction "VDDA_9") (pintype "unspecified"))
      (node (ref "U6") (pin "2") (pinfunction "VOUT_2") (pintype "unspecified"))
      (node (ref "U6") (pin "4") (pinfunction "VOUT_4") (pintype "unspecified"))
      (node (ref "U8") (pin "2") (pinfunction "VCC_2") (pintype "unspecified"))
      (node (ref "U9") (pin "3") (pinfunction "3_3") (pintype "unspecified"))
      (node (ref "U9") (pin "6") (pinfunction "6_6") (pintype "unspecified"))
    )
    (net (code "56") (name "unconnected-(SW2-Pad1)") (class "Default")
      (node (ref "SW2") (pin "1") (pinfunction "1_1") (pintype "unspecified"))
    )
    (net (code "57") (name "unconnected-(SW2-Pad2)") (class "Default")
      (node (ref "SW2") (pin "2") (pinfunction "2_2") (pintype "unspecified"))
    )
    (net (code "58") (name "unconnected-(SW2-Pad3)") (class "Default")
      (node (ref "SW2") (pin "3") (pinfunction "3_3") (pintype "unspecified"))
    )
    (net (code "59") (name "unconnected-(U10-Pad2)") (class "Default")
      (node (ref "U10") (pin "2") (pinfunction "2_2") (pintype "unspecified"))
    )
    (net (code "60") (name "unconnected-(U10-Pad3)") (class "Default")
      (node (ref "U10") (pin "3") (pinfunction "3_3") (pintype "unspecified"))
    )
    (net (code "61") (name "unconnected-(U11-Pad2)") (class "Default")
      (node (ref "U11") (pin "2") (pinfunction "2_2") (pintype "unspecified"))
    )
    (net (code "62") (name "unconnected-(U11-Pad3)") (class "Default")
      (node (ref "U11") (pin "3") (pinfunction "3_3") (pintype "unspecified"))
    )
    (net (code "63") (name "unconnected-(U12-Pad2)") (class "Default")
      (node (ref "U12") (pin "2") (pinfunction "2_2") (pintype "unspecified"))
    )
    (net (code "64") (name "unconnected-(U12-Pad3)") (class "Default")
      (node (ref "U12") (pin "3") (pinfunction "3_3") (pintype "unspecified"))
    )
    (net (code "65") (name "unconnected-(U13-Pad2)") (class "Default")
      (node (ref "U13") (pin "2") (pinfunction "2_2") (pintype "unspecified"))
    )
    (net (code "66") (name "unconnected-(U13-Pad3)") (class "Default")
      (node (ref "U13") (pin "3") (pinfunction "3_3") (pintype "unspecified"))
    )
    (net (code "67") (name "unconnected-(U14-Pad2)") (class "Default")
      (node (ref "U14") (pin "2") (pinfunction "2_2") (pintype "unspecified"))
    )
    (net (code "68") (name "unconnected-(U14-Pad3)") (class "Default")
      (node (ref "U14") (pin "3") (pinfunction "3_3") (pintype "unspecified"))
    )
    (net (code "69") (name "unconnected-(U15-Pad2)") (class "Default")
      (node (ref "U15") (pin "2") (pinfunction "2_2") (pintype "unspecified"))
    )
    (net (code "70") (name "unconnected-(U15-Pad3)") (class "Default")
      (node (ref "U15") (pin "3") (pinfunction "3_3") (pintype "unspecified"))
    )
    (net (code "71") (name "unconnected-(U16-Pad4)") (class "Default")
      (node (ref "U16") (pin "4") (pinfunction "4_4") (pintype "unspecified"))
    )
    (net (code "72") (name "unconnected-(U16-Pad5)") (class "Default")
      (node (ref "U16") (pin "5") (pinfunction "5_5") (pintype "unspecified"))
    )
  )
)
